# io-board-a-5.net
KiCad netlist of a schematic drawn in EAGLE
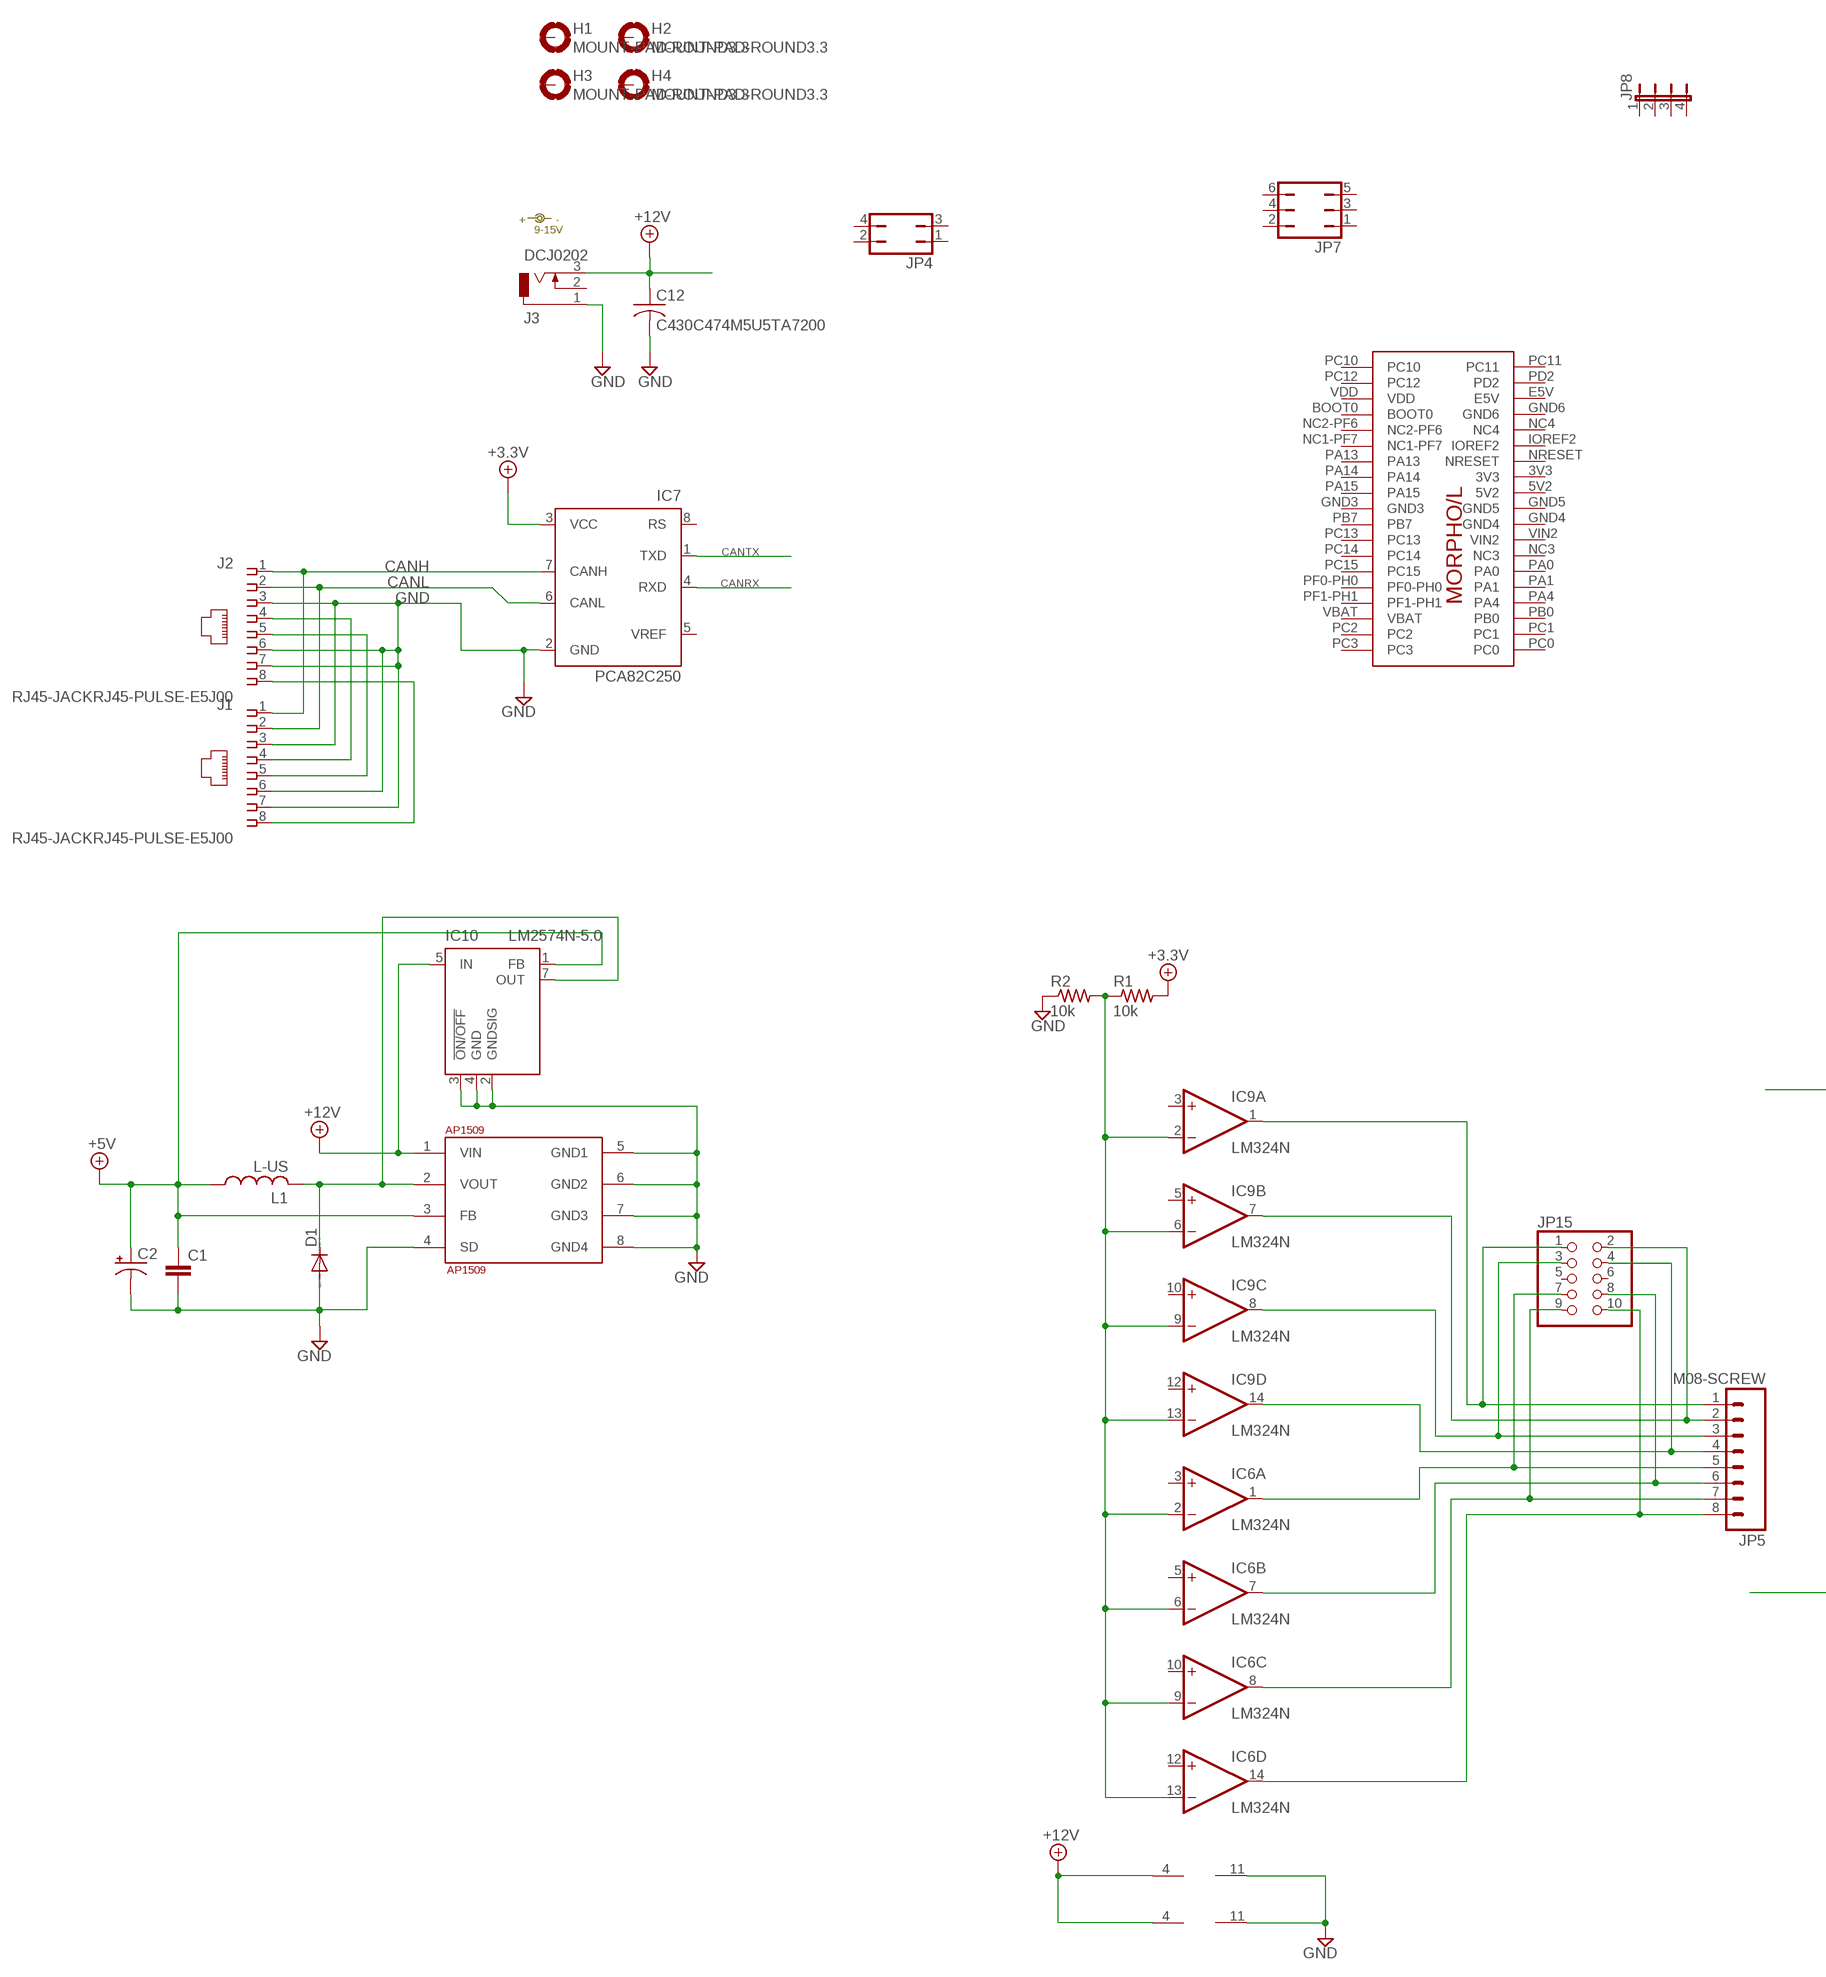
[diagram p0: schematic, sheet 1, part 1 of 2]
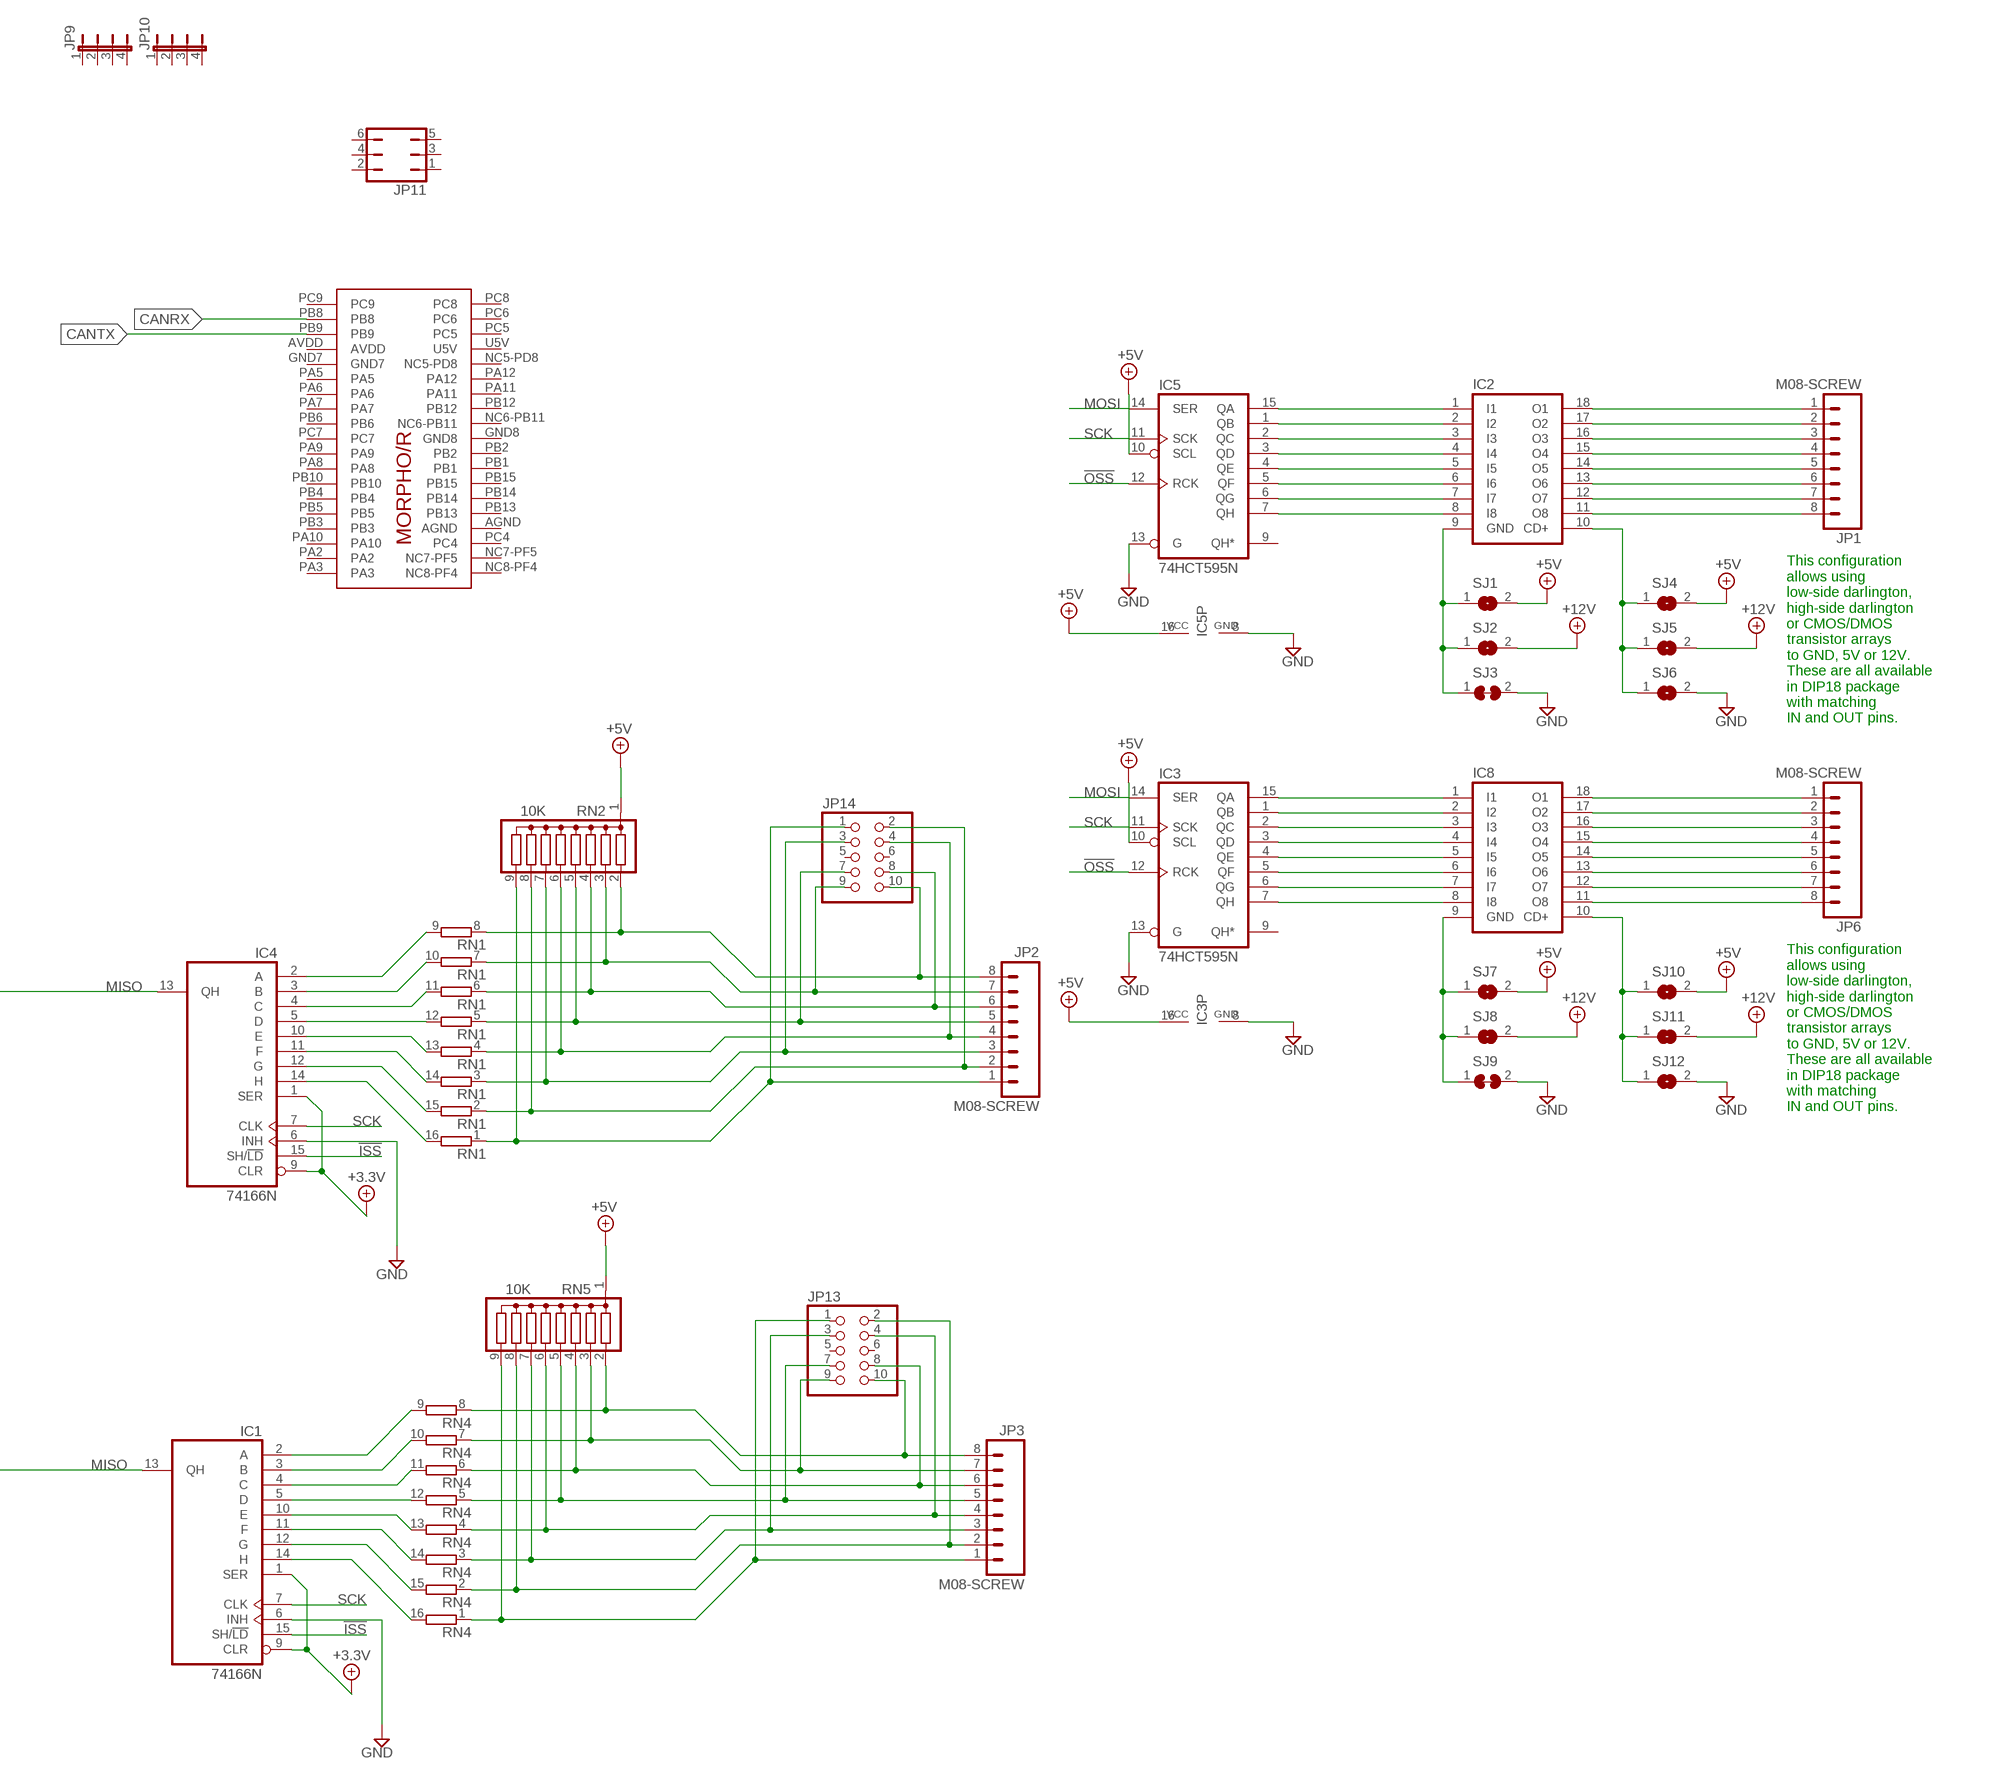
[diagram p1: schematic, sheet 1, part 2 of 2]

(export (version "E")
  (design (tool "Eeschema 10.0.6"))
  (components
    (comp (ref "+12V")
      (value "9-15V")
      (footprint "eagle-import:POWER_USAGE")
      (libsource (lib "eagle-import") (part "DOC-POWER_LABEL"))
    )
    (comp (ref "AP1509")
      (value "AP1509")
      (footprint "eagle-import:SO-08")
      (libsource (lib "eagle-import") (part "AP1509"))
    )
    (comp (ref "C1")
      (value "C-EUC1206")
      (footprint "eagle-import:C1206")
      (libsource (lib "eagle-import") (part "C-EUC1206"))
    )
    (comp (ref "C2")
      (value "CPOL-USE2.5-5")
      (footprint "eagle-import:E2,5-5")
      (libsource (lib "eagle-import") (part "CPOL-USE2.5-5"))
    )
    (comp (ref "C12")
      (value "C430C474M5U5TA7200")
      (footprint "eagle-import:C075-032X103")
      (libsource (lib "eagle-import") (part "C-US075-032X103"))
    )
    (comp (ref "D1")
      (value "DIODE-DO41-7.6")
      (footprint "eagle-import:DO41-7.6")
      (libsource (lib "eagle-import") (part "DIODE-DO41-7.6"))
    )
    (comp (ref "H1")
      (value "MOUNT-PAD-ROUND3.3")
      (footprint "eagle-import:3,3-PAD")
      (libsource (lib "eagle-import") (part "MOUNT-PAD-ROUND3.3"))
    )
    (comp (ref "H2")
      (value "MOUNT-PAD-ROUND3.3")
      (footprint "eagle-import:3,3-PAD")
      (libsource (lib "eagle-import") (part "MOUNT-PAD-ROUND3.3"))
    )
    (comp (ref "H3")
      (value "MOUNT-PAD-ROUND3.3")
      (footprint "eagle-import:3,3-PAD")
      (libsource (lib "eagle-import") (part "MOUNT-PAD-ROUND3.3"))
    )
    (comp (ref "H4")
      (value "MOUNT-PAD-ROUND3.3")
      (footprint "eagle-import:3,3-PAD")
      (libsource (lib "eagle-import") (part "MOUNT-PAD-ROUND3.3"))
    )
    (comp (ref "IC1")
      (value "74166N")
      (footprint "eagle-import:DIL16")
      (libsource (lib "eagle-import") (part "74166N"))
    )
    (comp (ref "IC2")
      (value "ULN2803A")
      (footprint "eagle-import:DIL18")
      (libsource (lib "eagle-import") (part "ULN2803A"))
    )
    (comp (ref "IC3")
      (value "74HCT595N")
      (footprint "eagle-import:DIL16")
      (libsource (lib "eagle-import") (part "74595NHCT"))
    )
    (comp (ref "IC4")
      (value "74166N")
      (footprint "eagle-import:DIL16")
      (libsource (lib "eagle-import") (part "74166N"))
    )
    (comp (ref "IC5")
      (value "74HCT595N")
      (footprint "eagle-import:DIL16")
      (libsource (lib "eagle-import") (part "74595NHCT"))
    )
    (comp (ref "IC6")
      (value "LM324N")
      (footprint "eagle-import:DIL14")
      (libsource (lib "eagle-import") (part "LM324N"))
    )
    (comp (ref "IC7")
      (value "PCA82C250")
      (footprint "eagle-import:DIL08")
      (libsource (lib "eagle-import") (part "PCA82C250"))
    )
    (comp (ref "IC8")
      (value "ULN2803A")
      (footprint "eagle-import:DIL18")
      (libsource (lib "eagle-import") (part "ULN2803A"))
    )
    (comp (ref "IC9")
      (value "LM324N")
      (footprint "eagle-import:DIL14")
      (libsource (lib "eagle-import") (part "LM324N"))
    )
    (comp (ref "IC10")
      (value "LM2574N-5.0")
      (footprint "eagle-import:DIL08")
      (libsource (lib "eagle-import") (part "LM2574?-N5.0"))
    )
    (comp (ref "J1")
      (value "RJ45-JACKRJ45-PULSE-E5J00")
      (footprint "eagle-import:RJ45-PULSE-E5J88")
      (libsource (lib "eagle-import") (part "RJ45-JACKRJ45-PULSE-E5J00"))
    )
    (comp (ref "J2")
      (value "RJ45-JACKRJ45-PULSE-E5J00")
      (footprint "eagle-import:RJ45-PULSE-E5J88")
      (libsource (lib "eagle-import") (part "RJ45-JACKRJ45-PULSE-E5J00"))
    )
    (comp (ref "J3")
      (value "DCJ0202")
      (footprint "eagle-import:DCJ0202")
      (libsource (lib "eagle-import") (part "DCJ0202"))
    )
    (comp (ref "JP1")
      (value "M08-SCREW")
      (footprint "eagle-import:1X08_TERMINAL")
      (libsource (lib "eagle-import") (part "M08-SCREW"))
    )
    (comp (ref "JP2")
      (value "M08-SCREW")
      (footprint "eagle-import:1X08_TERMINAL")
      (libsource (lib "eagle-import") (part "M08-SCREW"))
    )
    (comp (ref "JP3")
      (value "M08-SCREW")
      (footprint "eagle-import:1X08_TERMINAL")
      (libsource (lib "eagle-import") (part "M08-SCREW"))
    )
    (comp (ref "JP4")
      (value "JP2Q")
      (footprint "eagle-import:JP2Q")
      (libsource (lib "eagle-import") (part "JP2Q"))
    )
    (comp (ref "JP5")
      (value "M08-SCREW")
      (footprint "eagle-import:1X08_TERMINAL")
      (libsource (lib "eagle-import") (part "M08-SCREW"))
    )
    (comp (ref "JP6")
      (value "M08-SCREW")
      (footprint "eagle-import:1X08_TERMINAL")
      (libsource (lib "eagle-import") (part "M08-SCREW"))
    )
    (comp (ref "JP7")
      (value "JP3Q")
      (footprint "eagle-import:JP3Q")
      (libsource (lib "eagle-import") (part "JP3Q"))
    )
    (comp (ref "JP8")
      (value "JP4-FLAT")
      (footprint "eagle-import:JP4F")
      (libsource (lib "eagle-import") (part "JP4-FLAT"))
    )
    (comp (ref "JP9")
      (value "JP4-FLAT")
      (footprint "eagle-import:JP4F")
      (libsource (lib "eagle-import") (part "JP4-FLAT"))
    )
    (comp (ref "JP10")
      (value "JP4-FLAT")
      (footprint "eagle-import:JP4F")
      (libsource (lib "eagle-import") (part "JP4-FLAT"))
    )
    (comp (ref "JP11")
      (value "JP3Q")
      (footprint "eagle-import:JP3Q")
      (libsource (lib "eagle-import") (part "JP3Q"))
    )
    (comp (ref "JP13")
      (value "PINHD-2X5CN")
      (footprint "eagle-import:CON10M")
      (libsource (lib "eagle-import") (part "PINHD-2X5CN"))
    )
    (comp (ref "JP14")
      (value "PINHD-2X5CN")
      (footprint "eagle-import:CON10M")
      (libsource (lib "eagle-import") (part "PINHD-2X5CN"))
    )
    (comp (ref "JP15")
      (value "PINHD-2X5CN")
      (footprint "eagle-import:CON10M")
      (libsource (lib "eagle-import") (part "PINHD-2X5CN"))
    )
    (comp (ref "L1")
      (value "L-US")
      (footprint "eagle-import:L5-8,5")
      (libsource (lib "eagle-import") (part "L-US"))
    )
    (comp (ref "R1")
      (value "10k")
      (footprint "eagle-import:R1206")
      (libsource (lib "eagle-import") (part "R-US_R1206"))
    )
    (comp (ref "R2")
      (value "10k")
      (footprint "eagle-import:R1206")
      (libsource (lib "eagle-import") (part "R-US_R1206"))
    )
    (comp (ref "RN1")
      (value "8R-P")
      (footprint "eagle-import:DIL16")
      (libsource (lib "eagle-import") (part "8R-P"))
    )
    (comp (ref "RN2")
      (value "10K")
      (footprint "eagle-import:SIL9")
      (libsource (lib "eagle-import") (part "G08R"))
    )
    (comp (ref "RN4")
      (value "8R-P")
      (footprint "eagle-import:DIL16")
      (libsource (lib "eagle-import") (part "8R-P"))
    )
    (comp (ref "RN5")
      (value "10K")
      (footprint "eagle-import:SIL9")
      (libsource (lib "eagle-import") (part "G08R"))
    )
    (comp (ref "SJ1")
      (value "SJ")
      (footprint "eagle-import:SJ-RND")
      (libsource (lib "eagle-import") (part "SJ"))
    )
    (comp (ref "SJ2")
      (value "SJ")
      (footprint "eagle-import:SJ-RND")
      (libsource (lib "eagle-import") (part "SJ"))
    )
    (comp (ref "SJ3")
      (value "SJ-C")
      (footprint "eagle-import:SJW-C")
      (libsource (lib "eagle-import") (part "SJ-C"))
    )
    (comp (ref "SJ4")
      (value "SJ")
      (footprint "eagle-import:SJ-RND")
      (libsource (lib "eagle-import") (part "SJ"))
    )
    (comp (ref "SJ5")
      (value "SJ")
      (footprint "eagle-import:SJ-RND")
      (libsource (lib "eagle-import") (part "SJ"))
    )
    (comp (ref "SJ6")
      (value "SJ")
      (footprint "eagle-import:SJ-RND")
      (libsource (lib "eagle-import") (part "SJ"))
    )
    (comp (ref "SJ7")
      (value "SJ")
      (footprint "eagle-import:SJ-RND")
      (libsource (lib "eagle-import") (part "SJ"))
    )
    (comp (ref "SJ8")
      (value "SJ")
      (footprint "eagle-import:SJ-RND")
      (libsource (lib "eagle-import") (part "SJ"))
    )
    (comp (ref "SJ9")
      (value "SJ-C")
      (footprint "eagle-import:SJW-C")
      (libsource (lib "eagle-import") (part "SJ-C"))
    )
    (comp (ref "SJ10")
      (value "SJ")
      (footprint "eagle-import:SJ-RND")
      (libsource (lib "eagle-import") (part "SJ"))
    )
    (comp (ref "SJ11")
      (value "SJ")
      (footprint "eagle-import:SJ-RND")
      (libsource (lib "eagle-import") (part "SJ"))
    )
    (comp (ref "SJ12")
      (value "SJ")
      (footprint "eagle-import:SJ-RND")
      (libsource (lib "eagle-import") (part "SJ"))
    )
    (comp (ref "U$1")
      (value "NUCLEO_64_GENERIC")
      (footprint "eagle-import:NUCLEO_BRD_BASE64")
      (libsource (lib "eagle-import") (part "NUCLEO_64_GENERIC"))
    )
  )
  (nets
    (net (code "1") (name "+3.3V") (class "Default")
      (node (ref "IC1") (pin "1") (pinfunction "SER_1") (pintype "input"))
      (node (ref "IC1") (pin "9") (pinfunction "CLR_9") (pintype "input"))
      (node (ref "IC4") (pin "1") (pinfunction "SER_1") (pintype "input"))
      (node (ref "IC4") (pin "9") (pinfunction "CLR_9") (pintype "input"))
      (node (ref "IC7") (pin "3") (pinfunction "VCC_3") (pintype "power_in"))
      (node (ref "R1") (pin "2") (pinfunction "2_2") (pintype "passive"))
    )
    (net (code "2") (name "+5V") (class "Default")
      (node (ref "AP1509") (pin "3") (pinfunction "FB_3") (pintype "bidirectional"))
      (node (ref "C1") (pin "1") (pinfunction "1_1") (pintype "passive"))
      (node (ref "C2") (pin "+") (pinfunction "+_+") (pintype "passive"))
      (node (ref "IC10") (pin "1") (pinfunction "FB_1") (pintype "input"))
      (node (ref "IC3") (pin "10") (pinfunction "SCL_10") (pintype "input"))
      (node (ref "IC3") (pin "16") (pinfunction "VCC_16") (pintype "power_in"))
      (node (ref "IC5") (pin "10") (pinfunction "SCL_10") (pintype "input"))
      (node (ref "IC5") (pin "16") (pinfunction "VCC_16") (pintype "power_in"))
      (node (ref "L1") (pin "1") (pinfunction "1_1") (pintype "passive"))
      (node (ref "RN2") (pin "1") (pinfunction "1_1") (pintype "passive"))
      (node (ref "RN5") (pin "1") (pinfunction "1_1") (pintype "passive"))
      (node (ref "SJ1") (pin "2") (pinfunction "2_2") (pintype "passive"))
      (node (ref "SJ10") (pin "2") (pinfunction "2_2") (pintype "passive"))
      (node (ref "SJ4") (pin "2") (pinfunction "2_2") (pintype "passive"))
      (node (ref "SJ7") (pin "2") (pinfunction "2_2") (pintype "passive"))
    )
    (net (code "3") (name "+12V") (class "Default")
      (node (ref "AP1509") (pin "1") (pinfunction "VIN_1") (pintype "bidirectional"))
      (node (ref "C12") (pin "1") (pinfunction "1_1") (pintype "passive"))
      (node (ref "IC10") (pin "5") (pinfunction "IN_5") (pintype "input"))
      (node (ref "IC6") (pin "4") (pinfunction "V+_4") (pintype "power_in"))
      (node (ref "IC9") (pin "4") (pinfunction "V+_4") (pintype "power_in"))
      (node (ref "J3") (pin "3") (pinfunction "3_3") (pintype "passive"))
      (node (ref "SJ11") (pin "2") (pinfunction "2_2") (pintype "passive"))
      (node (ref "SJ2") (pin "2") (pinfunction "2_2") (pintype "passive"))
      (node (ref "SJ5") (pin "2") (pinfunction "2_2") (pintype "passive"))
      (node (ref "SJ8") (pin "2") (pinfunction "2_2") (pintype "passive"))
    )
    (net (code "4") (name "/3V3") (class "Default")
      (node (ref "U$1") (pin "3V3") (pinfunction "3V3_3V3") (pintype "power_in"))
    )
    (net (code "5") (name "/5V2") (class "Default")
      (node (ref "U$1") (pin "5V2") (pinfunction "5V2_5V2") (pintype "power_in"))
    )
    (net (code "6") (name "/AGND") (class "Default")
      (node (ref "U$1") (pin "AGND") (pinfunction "AGND_AGND") (pintype "power_in"))
    )
    (net (code "7") (name "/AVDD") (class "Default")
      (node (ref "U$1") (pin "AVDD") (pinfunction "AVDD_AVDD") (pintype "power_in"))
    )
    (net (code "8") (name "/CANH") (class "Default")
      (node (ref "IC7") (pin "7") (pinfunction "CANH_7") (pintype "bidirectional"))
      (node (ref "J1") (pin "1") (pinfunction "1_1") (pintype "passive"))
      (node (ref "J2") (pin "1") (pinfunction "1_1") (pintype "passive"))
    )
    (net (code "9") (name "/CANL") (class "Default")
      (node (ref "IC7") (pin "6") (pinfunction "CANL_6") (pintype "bidirectional"))
      (node (ref "J1") (pin "2") (pinfunction "2_2") (pintype "passive"))
      (node (ref "J2") (pin "2") (pinfunction "2_2") (pintype "passive"))
    )
    (net (code "10") (name "/E5V") (class "Default")
      (node (ref "U$1") (pin "E5V") (pinfunction "E5V_E5V") (pintype "power_in"))
    )
    (net (code "11") (name "/GND3") (class "Default")
      (node (ref "U$1") (pin "GND3") (pinfunction "GND3_GND3") (pintype "power_in"))
    )
    (net (code "12") (name "/GND4") (class "Default")
      (node (ref "U$1") (pin "GND4") (pinfunction "GND4_GND4") (pintype "power_in"))
    )
    (net (code "13") (name "/GND5") (class "Default")
      (node (ref "U$1") (pin "GND5") (pinfunction "GND5_GND5") (pintype "power_in"))
    )
    (net (code "14") (name "/GND6") (class "Default")
      (node (ref "U$1") (pin "GND6") (pinfunction "GND6_GND6") (pintype "power_in"))
    )
    (net (code "15") (name "/GND7") (class "Default")
      (node (ref "U$1") (pin "GND7") (pinfunction "GND7_GND7") (pintype "power_in"))
    )
    (net (code "16") (name "/GND8") (class "Default")
      (node (ref "U$1") (pin "GND8") (pinfunction "GND8_GND8") (pintype "power_in"))
    )
    (net (code "17") (name "/MISO") (class "Default")
      (node (ref "IC1") (pin "13") (pinfunction "QH_13") (pintype "output"))
      (node (ref "IC4") (pin "13") (pinfunction "QH_13") (pintype "output"))
    )
    (net (code "18") (name "/MOSI") (class "Default")
      (node (ref "IC3") (pin "14") (pinfunction "SER_14") (pintype "input"))
      (node (ref "IC5") (pin "14") (pinfunction "SER_14") (pintype "input"))
    )
    (net (code "19") (name "/SCK") (class "Default")
      (node (ref "IC1") (pin "7") (pinfunction "CLK_7") (pintype "input"))
      (node (ref "IC3") (pin "11") (pinfunction "SCK_11") (pintype "input"))
      (node (ref "IC4") (pin "7") (pinfunction "CLK_7") (pintype "input"))
      (node (ref "IC5") (pin "11") (pinfunction "SCK_11") (pintype "input"))
    )
    (net (code "20") (name "/U5V") (class "Default")
      (node (ref "U$1") (pin "U5V") (pinfunction "U5V_U5V") (pintype "power_in"))
    )
    (net (code "21") (name "/VBAT") (class "Default")
      (node (ref "U$1") (pin "VBAT") (pinfunction "VBAT_VBAT") (pintype "power_in"))
    )
    (net (code "22") (name "/VDD") (class "Default")
      (node (ref "U$1") (pin "VDD") (pinfunction "VDD_VDD") (pintype "power_in"))
    )
    (net (code "23") (name "/VIN2") (class "Default")
      (node (ref "U$1") (pin "VIN2") (pinfunction "VIN2_VIN2") (pintype "power_in"))
    )
    (net (code "24") (name "/~{ISS}") (class "Default")
      (node (ref "IC1") (pin "15") (pinfunction "SH/~{LD}_15") (pintype "input"))
      (node (ref "IC4") (pin "15") (pinfunction "SH/~{LD}_15") (pintype "input"))
    )
    (net (code "25") (name "/~{OSS}") (class "Default")
      (node (ref "IC3") (pin "12") (pinfunction "RCK_12") (pintype "input"))
      (node (ref "IC5") (pin "12") (pinfunction "RCK_12") (pintype "input"))
    )
    (net (code "26") (name "CANRX") (class "Default")
      (node (ref "IC7") (pin "4") (pinfunction "RXD_4") (pintype "output"))
      (node (ref "U$1") (pin "PB8") (pinfunction "PB8_PB8") (pintype "bidirectional"))
    )
    (net (code "27") (name "CANTX") (class "Default")
      (node (ref "IC7") (pin "1") (pinfunction "TXD_1") (pintype "input"))
      (node (ref "U$1") (pin "PB9") (pinfunction "PB9_PB9") (pintype "bidirectional"))
    )
    (net (code "28") (name "GND") (class "Default")
      (node (ref "AP1509") (pin "4") (pinfunction "SD_4") (pintype "bidirectional"))
      (node (ref "AP1509") (pin "5") (pinfunction "GND1_5") (pintype "power_in"))
      (node (ref "AP1509") (pin "6") (pinfunction "GND2_6") (pintype "power_in"))
      (node (ref "AP1509") (pin "7") (pinfunction "GND3_7") (pintype "power_in"))
      (node (ref "AP1509") (pin "8") (pinfunction "GND4_8") (pintype "power_in"))
      (node (ref "C1") (pin "2") (pinfunction "2_2") (pintype "passive"))
      (node (ref "C12") (pin "2") (pinfunction "2_2") (pintype "passive"))
      (node (ref "C2") (pin "-") (pinfunction "-_-") (pintype "passive"))
      (node (ref "D1") (pin "A") (pinfunction "A_A") (pintype "passive"))
      (node (ref "IC1") (pin "6") (pinfunction "INH_6") (pintype "input"))
      (node (ref "IC10") (pin "2") (pinfunction "GNDSIG_2") (pintype "input"))
      (node (ref "IC10") (pin "3") (pinfunction "~{ON/OFF}_3") (pintype "input"))
      (node (ref "IC10") (pin "4") (pinfunction "GND_4") (pintype "power_in"))
      (node (ref "IC3") (pin "13") (pinfunction "G_13") (pintype "input"))
      (node (ref "IC3") (pin "8") (pinfunction "GND_8") (pintype "power_in"))
      (node (ref "IC4") (pin "6") (pinfunction "INH_6") (pintype "input"))
      (node (ref "IC5") (pin "13") (pinfunction "G_13") (pintype "input"))
      (node (ref "IC5") (pin "8") (pinfunction "GND_8") (pintype "power_in"))
      (node (ref "IC6") (pin "11") (pinfunction "V-_11") (pintype "power_in"))
      (node (ref "IC7") (pin "2") (pinfunction "GND_2") (pintype "power_in"))
      (node (ref "IC9") (pin "11") (pinfunction "V-_11") (pintype "power_in"))
      (node (ref "J1") (pin "3") (pinfunction "3_3") (pintype "passive"))
      (node (ref "J1") (pin "6") (pinfunction "6_6") (pintype "passive"))
      (node (ref "J1") (pin "7") (pinfunction "7_7") (pintype "passive"))
      (node (ref "J2") (pin "3") (pinfunction "3_3") (pintype "passive"))
      (node (ref "J2") (pin "6") (pinfunction "6_6") (pintype "passive"))
      (node (ref "J2") (pin "7") (pinfunction "7_7") (pintype "passive"))
      (node (ref "J3") (pin "1") (pinfunction "1_1") (pintype "passive"))
      (node (ref "R2") (pin "1") (pinfunction "1_1") (pintype "passive"))
      (node (ref "SJ12") (pin "2") (pinfunction "2_2") (pintype "passive"))
      (node (ref "SJ3") (pin "2") (pinfunction "2_2") (pintype "passive"))
      (node (ref "SJ6") (pin "2") (pinfunction "2_2") (pintype "passive"))
      (node (ref "SJ9") (pin "2") (pinfunction "2_2") (pintype "passive"))
    )
    (net (code "29") (name "Net-(AP1509-VOUT)") (class "Default")
      (node (ref "AP1509") (pin "2") (pinfunction "VOUT_2") (pintype "bidirectional"))
      (node (ref "D1") (pin "C") (pinfunction "C_C") (pintype "passive"))
      (node (ref "IC10") (pin "7") (pinfunction "OUT_7") (pintype "passive"))
      (node (ref "L1") (pin "2") (pinfunction "2_2") (pintype "passive"))
    )
    (net (code "30") (name "Net-(IC1A-A)") (class "Default")
      (node (ref "IC1") (pin "2") (pinfunction "A_2") (pintype "input"))
      (node (ref "RN4") (pin "9") (pinfunction "2_9") (pintype "passive"))
    )
    (net (code "31") (name "Net-(IC1A-B)") (class "Default")
      (node (ref "IC1") (pin "3") (pinfunction "B_3") (pintype "input"))
      (node (ref "RN4") (pin "10") (pinfunction "2_10") (pintype "passive"))
    )
    (net (code "32") (name "Net-(IC1A-C)") (class "Default")
      (node (ref "IC1") (pin "4") (pinfunction "C_4") (pintype "input"))
      (node (ref "RN4") (pin "11") (pinfunction "2_11") (pintype "passive"))
    )
    (net (code "33") (name "Net-(IC1A-D)") (class "Default")
      (node (ref "IC1") (pin "5") (pinfunction "D_5") (pintype "input"))
      (node (ref "RN4") (pin "12") (pinfunction "2_12") (pintype "passive"))
    )
    (net (code "34") (name "Net-(IC1A-E)") (class "Default")
      (node (ref "IC1") (pin "10") (pinfunction "E_10") (pintype "input"))
      (node (ref "RN4") (pin "13") (pinfunction "2_13") (pintype "passive"))
    )
    (net (code "35") (name "Net-(IC1A-F)") (class "Default")
      (node (ref "IC1") (pin "11") (pinfunction "F_11") (pintype "input"))
      (node (ref "RN4") (pin "14") (pinfunction "2_14") (pintype "passive"))
    )
    (net (code "36") (name "Net-(IC1A-G)") (class "Default")
      (node (ref "IC1") (pin "12") (pinfunction "G_12") (pintype "input"))
      (node (ref "RN4") (pin "15") (pinfunction "2_15") (pintype "passive"))
    )
    (net (code "37") (name "Net-(IC1A-H)") (class "Default")
      (node (ref "IC1") (pin "14") (pinfunction "H_14") (pintype "input"))
      (node (ref "RN4") (pin "16") (pinfunction "2_16") (pintype "passive"))
    )
    (net (code "38") (name "Net-(IC2-CD+)") (class "Default")
      (node (ref "IC2") (pin "10") (pinfunction "CD+_10") (pintype "passive"))
      (node (ref "SJ4") (pin "1") (pinfunction "1_1") (pintype "passive"))
      (node (ref "SJ5") (pin "1") (pinfunction "1_1") (pintype "passive"))
      (node (ref "SJ6") (pin "1") (pinfunction "1_1") (pintype "passive"))
    )
    (net (code "39") (name "Net-(IC2-GND)") (class "Default")
      (node (ref "IC2") (pin "9") (pinfunction "GND_9") (pintype "power_in"))
      (node (ref "SJ1") (pin "1") (pinfunction "1_1") (pintype "passive"))
      (node (ref "SJ2") (pin "1") (pinfunction "1_1") (pintype "passive"))
      (node (ref "SJ3") (pin "1") (pinfunction "1_1") (pintype "passive"))
    )
    (net (code "40") (name "Net-(IC2-I1)") (class "Default")
      (node (ref "IC2") (pin "1") (pinfunction "I1_1") (pintype "input"))
      (node (ref "IC5") (pin "15") (pinfunction "QA_15") (pintype "tri_state"))
    )
    (net (code "41") (name "Net-(IC2-I2)") (class "Default")
      (node (ref "IC2") (pin "2") (pinfunction "I2_2") (pintype "input"))
      (node (ref "IC5") (pin "1") (pinfunction "QB_1") (pintype "tri_state"))
    )
    (net (code "42") (name "Net-(IC2-I3)") (class "Default")
      (node (ref "IC2") (pin "3") (pinfunction "I3_3") (pintype "input"))
      (node (ref "IC5") (pin "2") (pinfunction "QC_2") (pintype "tri_state"))
    )
    (net (code "43") (name "Net-(IC2-I4)") (class "Default")
      (node (ref "IC2") (pin "4") (pinfunction "I4_4") (pintype "input"))
      (node (ref "IC5") (pin "3") (pinfunction "QD_3") (pintype "tri_state"))
    )
    (net (code "44") (name "Net-(IC2-I5)") (class "Default")
      (node (ref "IC2") (pin "5") (pinfunction "I5_5") (pintype "input"))
      (node (ref "IC5") (pin "4") (pinfunction "QE_4") (pintype "tri_state"))
    )
    (net (code "45") (name "Net-(IC2-I6)") (class "Default")
      (node (ref "IC2") (pin "6") (pinfunction "I6_6") (pintype "input"))
      (node (ref "IC5") (pin "5") (pinfunction "QF_5") (pintype "tri_state"))
    )
    (net (code "46") (name "Net-(IC2-I7)") (class "Default")
      (node (ref "IC2") (pin "7") (pinfunction "I7_7") (pintype "input"))
      (node (ref "IC5") (pin "6") (pinfunction "QG_6") (pintype "tri_state"))
    )
    (net (code "47") (name "Net-(IC2-I8)") (class "Default")
      (node (ref "IC2") (pin "8") (pinfunction "I8_8") (pintype "input"))
      (node (ref "IC5") (pin "7") (pinfunction "QH_7") (pintype "tri_state"))
    )
    (net (code "48") (name "Net-(IC2-O1)") (class "Default")
      (node (ref "IC2") (pin "18") (pinfunction "O1_18") (pintype "open_collector"))
      (node (ref "JP1") (pin "1") (pinfunction "1_1") (pintype "passive"))
    )
    (net (code "49") (name "Net-(IC2-O2)") (class "Default")
      (node (ref "IC2") (pin "17") (pinfunction "O2_17") (pintype "open_collector"))
      (node (ref "JP1") (pin "2") (pinfunction "2_2") (pintype "passive"))
    )
    (net (code "50") (name "Net-(IC2-O3)") (class "Default")
      (node (ref "IC2") (pin "16") (pinfunction "O3_16") (pintype "open_collector"))
      (node (ref "JP1") (pin "3") (pinfunction "3_3") (pintype "passive"))
    )
    (net (code "51") (name "Net-(IC2-O4)") (class "Default")
      (node (ref "IC2") (pin "15") (pinfunction "O4_15") (pintype "open_collector"))
      (node (ref "JP1") (pin "4") (pinfunction "4_4") (pintype "passive"))
    )
    (net (code "52") (name "Net-(IC2-O5)") (class "Default")
      (node (ref "IC2") (pin "14") (pinfunction "O5_14") (pintype "open_collector"))
      (node (ref "JP1") (pin "5") (pinfunction "5_5") (pintype "passive"))
    )
    (net (code "53") (name "Net-(IC2-O6)") (class "Default")
      (node (ref "IC2") (pin "13") (pinfunction "O6_13") (pintype "open_collector"))
      (node (ref "JP1") (pin "6") (pinfunction "6_6") (pintype "passive"))
    )
    (net (code "54") (name "Net-(IC2-O7)") (class "Default")
      (node (ref "IC2") (pin "12") (pinfunction "O7_12") (pintype "open_collector"))
      (node (ref "JP1") (pin "7") (pinfunction "7_7") (pintype "passive"))
    )
    (net (code "55") (name "Net-(IC2-O8)") (class "Default")
      (node (ref "IC2") (pin "11") (pinfunction "O8_11") (pintype "open_collector"))
      (node (ref "JP1") (pin "8") (pinfunction "8_8") (pintype "passive"))
    )
    (net (code "56") (name "Net-(IC3A-QA)") (class "Default")
      (node (ref "IC3") (pin "15") (pinfunction "QA_15") (pintype "tri_state"))
      (node (ref "IC8") (pin "1") (pinfunction "I1_1") (pintype "input"))
    )
    (net (code "57") (name "Net-(IC3A-QB)") (class "Default")
      (node (ref "IC3") (pin "1") (pinfunction "QB_1") (pintype "tri_state"))
      (node (ref "IC8") (pin "2") (pinfunction "I2_2") (pintype "input"))
    )
    (net (code "58") (name "Net-(IC3A-QC)") (class "Default")
      (node (ref "IC3") (pin "2") (pinfunction "QC_2") (pintype "tri_state"))
      (node (ref "IC8") (pin "3") (pinfunction "I3_3") (pintype "input"))
    )
    (net (code "59") (name "Net-(IC3A-QD)") (class "Default")
      (node (ref "IC3") (pin "3") (pinfunction "QD_3") (pintype "tri_state"))
      (node (ref "IC8") (pin "4") (pinfunction "I4_4") (pintype "input"))
    )
    (net (code "60") (name "Net-(IC3A-QE)") (class "Default")
      (node (ref "IC3") (pin "4") (pinfunction "QE_4") (pintype "tri_state"))
      (node (ref "IC8") (pin "5") (pinfunction "I5_5") (pintype "input"))
    )
    (net (code "61") (name "Net-(IC3A-QF)") (class "Default")
      (node (ref "IC3") (pin "5") (pinfunction "QF_5") (pintype "tri_state"))
      (node (ref "IC8") (pin "6") (pinfunction "I6_6") (pintype "input"))
    )
    (net (code "62") (name "Net-(IC3A-QG)") (class "Default")
      (node (ref "IC3") (pin "6") (pinfunction "QG_6") (pintype "tri_state"))
      (node (ref "IC8") (pin "7") (pinfunction "I7_7") (pintype "input"))
    )
    (net (code "63") (name "Net-(IC3A-QH)") (class "Default")
      (node (ref "IC3") (pin "7") (pinfunction "QH_7") (pintype "tri_state"))
      (node (ref "IC8") (pin "8") (pinfunction "I8_8") (pintype "input"))
    )
    (net (code "64") (name "Net-(IC4A-A)") (class "Default")
      (node (ref "IC4") (pin "2") (pinfunction "A_2") (pintype "input"))
      (node (ref "RN1") (pin "9") (pinfunction "2_9") (pintype "passive"))
    )
    (net (code "65") (name "Net-(IC4A-B)") (class "Default")
      (node (ref "IC4") (pin "3") (pinfunction "B_3") (pintype "input"))
      (node (ref "RN1") (pin "10") (pinfunction "2_10") (pintype "passive"))
    )
    (net (code "66") (name "Net-(IC4A-C)") (class "Default")
      (node (ref "IC4") (pin "4") (pinfunction "C_4") (pintype "input"))
      (node (ref "RN1") (pin "11") (pinfunction "2_11") (pintype "passive"))
    )
    (net (code "67") (name "Net-(IC4A-D)") (class "Default")
      (node (ref "IC4") (pin "5") (pinfunction "D_5") (pintype "input"))
      (node (ref "RN1") (pin "12") (pinfunction "2_12") (pintype "passive"))
    )
    (net (code "68") (name "Net-(IC4A-E)") (class "Default")
      (node (ref "IC4") (pin "10") (pinfunction "E_10") (pintype "input"))
      (node (ref "RN1") (pin "13") (pinfunction "2_13") (pintype "passive"))
    )
    (net (code "69") (name "Net-(IC4A-F)") (class "Default")
      (node (ref "IC4") (pin "11") (pinfunction "F_11") (pintype "input"))
      (node (ref "RN1") (pin "14") (pinfunction "2_14") (pintype "passive"))
    )
    (net (code "70") (name "Net-(IC4A-G)") (class "Default")
      (node (ref "IC4") (pin "12") (pinfunction "G_12") (pintype "input"))
      (node (ref "RN1") (pin "15") (pinfunction "2_15") (pintype "passive"))
    )
    (net (code "71") (name "Net-(IC4A-H)") (class "Default")
      (node (ref "IC4") (pin "14") (pinfunction "H_14") (pintype "input"))
      (node (ref "RN1") (pin "16") (pinfunction "2_16") (pintype "passive"))
    )
    (net (code "72") (name "Net-(IC6A--IN)") (class "Default")
      (node (ref "IC6") (pin "13") (pinfunction "-IN_13") (pintype "input"))
      (node (ref "IC6") (pin "2") (pinfunction "-IN_2") (pintype "input"))
      (node (ref "IC6") (pin "6") (pinfunction "-IN_6") (pintype "input"))
      (node (ref "IC6") (pin "9") (pinfunction "-IN_9") (pintype "input"))
      (node (ref "IC9") (pin "13") (pinfunction "-IN_13") (pintype "input"))
      (node (ref "IC9") (pin "2") (pinfunction "-IN_2") (pintype "input"))
      (node (ref "IC9") (pin "6") (pinfunction "-IN_6") (pintype "input"))
      (node (ref "IC9") (pin "9") (pinfunction "-IN_9") (pintype "input"))
      (node (ref "R1") (pin "1") (pinfunction "1_1") (pintype "passive"))
      (node (ref "R2") (pin "2") (pinfunction "2_2") (pintype "passive"))
    )
    (net (code "73") (name "Net-(IC6A-OUT)") (class "Default")
      (node (ref "IC6") (pin "1") (pinfunction "OUT_1") (pintype "output"))
      (node (ref "JP15") (pin "7") (pinfunction "7_7") (pintype "passive"))
      (node (ref "JP5") (pin "5") (pinfunction "5_5") (pintype "passive"))
    )
    (net (code "74") (name "Net-(IC6B-OUT)") (class "Default")
      (node (ref "IC6") (pin "7") (pinfunction "OUT_7") (pintype "output"))
      (node (ref "JP15") (pin "8") (pinfunction "8_8") (pintype "passive"))
      (node (ref "JP5") (pin "6") (pinfunction "6_6") (pintype "passive"))
    )
    (net (code "75") (name "Net-(IC6C-OUT)") (class "Default")
      (node (ref "IC6") (pin "8") (pinfunction "OUT_8") (pintype "output"))
      (node (ref "JP15") (pin "9") (pinfunction "9_9") (pintype "passive"))
      (node (ref "JP5") (pin "7") (pinfunction "7_7") (pintype "passive"))
    )
    (net (code "76") (name "Net-(IC6D-OUT)") (class "Default")
      (node (ref "IC6") (pin "14") (pinfunction "OUT_14") (pintype "output"))
      (node (ref "JP15") (pin "10") (pinfunction "10_10") (pintype "passive"))
      (node (ref "JP5") (pin "8") (pinfunction "8_8") (pintype "passive"))
    )
    (net (code "77") (name "Net-(IC8-CD+)") (class "Default")
      (node (ref "IC8") (pin "10") (pinfunction "CD+_10") (pintype "passive"))
      (node (ref "SJ10") (pin "1") (pinfunction "1_1") (pintype "passive"))
      (node (ref "SJ11") (pin "1") (pinfunction "1_1") (pintype "passive"))
      (node (ref "SJ12") (pin "1") (pinfunction "1_1") (pintype "passive"))
    )
    (net (code "78") (name "Net-(IC8-GND)") (class "Default")
      (node (ref "IC8") (pin "9") (pinfunction "GND_9") (pintype "power_in"))
      (node (ref "SJ7") (pin "1") (pinfunction "1_1") (pintype "passive"))
      (node (ref "SJ8") (pin "1") (pinfunction "1_1") (pintype "passive"))
      (node (ref "SJ9") (pin "1") (pinfunction "1_1") (pintype "passive"))
    )
    (net (code "79") (name "Net-(IC8-O1)") (class "Default")
      (node (ref "IC8") (pin "18") (pinfunction "O1_18") (pintype "open_collector"))
      (node (ref "JP6") (pin "1") (pinfunction "1_1") (pintype "passive"))
    )
    (net (code "80") (name "Net-(IC8-O2)") (class "Default")
      (node (ref "IC8") (pin "17") (pinfunction "O2_17") (pintype "open_collector"))
      (node (ref "JP6") (pin "2") (pinfunction "2_2") (pintype "passive"))
    )
    (net (code "81") (name "Net-(IC8-O3)") (class "Default")
      (node (ref "IC8") (pin "16") (pinfunction "O3_16") (pintype "open_collector"))
      (node (ref "JP6") (pin "3") (pinfunction "3_3") (pintype "passive"))
    )
    (net (code "82") (name "Net-(IC8-O4)") (class "Default")
      (node (ref "IC8") (pin "15") (pinfunction "O4_15") (pintype "open_collector"))
      (node (ref "JP6") (pin "4") (pinfunction "4_4") (pintype "passive"))
    )
    (net (code "83") (name "Net-(IC8-O5)") (class "Default")
      (node (ref "IC8") (pin "14") (pinfunction "O5_14") (pintype "open_collector"))
      (node (ref "JP6") (pin "5") (pinfunction "5_5") (pintype "passive"))
    )
    (net (code "84") (name "Net-(IC8-O6)") (class "Default")
      (node (ref "IC8") (pin "13") (pinfunction "O6_13") (pintype "open_collector"))
      (node (ref "JP6") (pin "6") (pinfunction "6_6") (pintype "passive"))
    )
    (net (code "85") (name "Net-(IC8-O7)") (class "Default")
      (node (ref "IC8") (pin "12") (pinfunction "O7_12") (pintype "open_collector"))
      (node (ref "JP6") (pin "7") (pinfunction "7_7") (pintype "passive"))
    )
    (net (code "86") (name "Net-(IC8-O8)") (class "Default")
      (node (ref "IC8") (pin "11") (pinfunction "O8_11") (pintype "open_collector"))
      (node (ref "JP6") (pin "8") (pinfunction "8_8") (pintype "passive"))
    )
    (net (code "87") (name "Net-(IC9A-OUT)") (class "Default")
      (node (ref "IC9") (pin "1") (pinfunction "OUT_1") (pintype "output"))
      (node (ref "JP15") (pin "1") (pinfunction "1_1") (pintype "passive"))
      (node (ref "JP5") (pin "1") (pinfunction "1_1") (pintype "passive"))
    )
    (net (code "88") (name "Net-(IC9B-OUT)") (class "Default")
      (node (ref "IC9") (pin "7") (pinfunction "OUT_7") (pintype "output"))
      (node (ref "JP15") (pin "2") (pinfunction "2_2") (pintype "passive"))
      (node (ref "JP5") (pin "2") (pinfunction "2_2") (pintype "passive"))
    )
    (net (code "89") (name "Net-(IC9C-OUT)") (class "Default")
      (node (ref "IC9") (pin "8") (pinfunction "OUT_8") (pintype "output"))
      (node (ref "JP15") (pin "3") (pinfunction "3_3") (pintype "passive"))
      (node (ref "JP5") (pin "3") (pinfunction "3_3") (pintype "passive"))
    )
    (net (code "90") (name "Net-(IC9D-OUT)") (class "Default")
      (node (ref "IC9") (pin "14") (pinfunction "OUT_14") (pintype "output"))
      (node (ref "JP15") (pin "4") (pinfunction "4_4") (pintype "passive"))
      (node (ref "JP5") (pin "4") (pinfunction "4_4") (pintype "passive"))
    )
    (net (code "91") (name "Net-(J1-Pad4)") (class "Default")
      (node (ref "J1") (pin "4") (pinfunction "4_4") (pintype "passive"))
      (node (ref "J2") (pin "4") (pinfunction "4_4") (pintype "passive"))
    )
    (net (code "92") (name "Net-(J1-Pad5)") (class "Default")
      (node (ref "J1") (pin "5") (pinfunction "5_5") (pintype "passive"))
      (node (ref "J2") (pin "5") (pinfunction "5_5") (pintype "passive"))
    )
    (net (code "93") (name "Net-(J1-Pad8)") (class "Default")
      (node (ref "J1") (pin "8") (pinfunction "8_8") (pintype "passive"))
      (node (ref "J2") (pin "8") (pinfunction "8_8") (pintype "passive"))
    )
    (net (code "94") (name "Net-(JP13-Pad1)") (class "Default")
      (node (ref "JP13") (pin "1") (pinfunction "1_1") (pintype "passive"))
      (node (ref "JP3") (pin "1") (pinfunction "1_1") (pintype "passive"))
      (node (ref "RN4") (pin "1") (pinfunction "1_1") (pintype "passive"))
      (node (ref "RN5") (pin "9") (pinfunction "9_9") (pintype "passive"))
    )
    (net (code "95") (name "Net-(JP14-Pad1)") (class "Default")
      (node (ref "JP14") (pin "1") (pinfunction "1_1") (pintype "passive"))
      (node (ref "JP2") (pin "1") (pinfunction "1_1") (pintype "passive"))
      (node (ref "RN1") (pin "1") (pinfunction "1_1") (pintype "passive"))
      (node (ref "RN2") (pin "9") (pinfunction "9_9") (pintype "passive"))
    )
    (net (code "96") (name "Net-(RN1B-1)") (class "Default")
      (node (ref "JP14") (pin "2") (pinfunction "2_2") (pintype "passive"))
      (node (ref "JP2") (pin "2") (pinfunction "2_2") (pintype "passive"))
      (node (ref "RN1") (pin "2") (pinfunction "1_2") (pintype "passive"))
      (node (ref "RN2") (pin "8") (pinfunction "8_8") (pintype "passive"))
    )
    (net (code "97") (name "Net-(RN1C-1)") (class "Default")
      (node (ref "JP14") (pin "3") (pinfunction "3_3") (pintype "passive"))
      (node (ref "JP2") (pin "3") (pinfunction "3_3") (pintype "passive"))
      (node (ref "RN1") (pin "3") (pinfunction "1_3") (pintype "passive"))
      (node (ref "RN2") (pin "7") (pinfunction "7_7") (pintype "passive"))
    )
    (net (code "98") (name "Net-(RN1D-1)") (class "Default")
      (node (ref "JP14") (pin "4") (pinfunction "4_4") (pintype "passive"))
      (node (ref "JP2") (pin "4") (pinfunction "4_4") (pintype "passive"))
      (node (ref "RN1") (pin "4") (pinfunction "1_4") (pintype "passive"))
      (node (ref "RN2") (pin "6") (pinfunction "6_6") (pintype "passive"))
    )
    (net (code "99") (name "Net-(RN1E-1)") (class "Default")
      (node (ref "JP14") (pin "7") (pinfunction "7_7") (pintype "passive"))
      (node (ref "JP2") (pin "5") (pinfunction "5_5") (pintype "passive"))
      (node (ref "RN1") (pin "5") (pinfunction "1_5") (pintype "passive"))
      (node (ref "RN2") (pin "5") (pinfunction "5_5") (pintype "passive"))
    )
    (net (code "100") (name "Net-(RN1F-1)") (class "Default")
      (node (ref "JP14") (pin "8") (pinfunction "8_8") (pintype "passive"))
      (node (ref "JP2") (pin "6") (pinfunction "6_6") (pintype "passive"))
      (node (ref "RN1") (pin "6") (pinfunction "1_6") (pintype "passive"))
      (node (ref "RN2") (pin "4") (pinfunction "4_4") (pintype "passive"))
    )
    (net (code "101") (name "Net-(RN1G-1)") (class "Default")
      (node (ref "JP14") (pin "9") (pinfunction "9_9") (pintype "passive"))
      (node (ref "JP2") (pin "7") (pinfunction "7_7") (pintype "passive"))
      (node (ref "RN1") (pin "7") (pinfunction "1_7") (pintype "passive"))
      (node (ref "RN2") (pin "3") (pinfunction "3_3") (pintype "passive"))
    )
    (net (code "102") (name "Net-(RN1H-1)") (class "Default")
      (node (ref "JP14") (pin "10") (pinfunction "10_10") (pintype "passive"))
      (node (ref "JP2") (pin "8") (pinfunction "8_8") (pintype "passive"))
      (node (ref "RN1") (pin "8") (pinfunction "1_8") (pintype "passive"))
      (node (ref "RN2") (pin "2") (pinfunction "2_2") (pintype "passive"))
    )
    (net (code "103") (name "Net-(RN4B-1)") (class "Default")
      (node (ref "JP13") (pin "2") (pinfunction "2_2") (pintype "passive"))
      (node (ref "JP3") (pin "2") (pinfunction "2_2") (pintype "passive"))
      (node (ref "RN4") (pin "2") (pinfunction "1_2") (pintype "passive"))
      (node (ref "RN5") (pin "8") (pinfunction "8_8") (pintype "passive"))
    )
    (net (code "104") (name "Net-(RN4C-1)") (class "Default")
      (node (ref "JP13") (pin "3") (pinfunction "3_3") (pintype "passive"))
      (node (ref "JP3") (pin "3") (pinfunction "3_3") (pintype "passive"))
      (node (ref "RN4") (pin "3") (pinfunction "1_3") (pintype "passive"))
      (node (ref "RN5") (pin "7") (pinfunction "7_7") (pintype "passive"))
    )
    (net (code "105") (name "Net-(RN4D-1)") (class "Default")
      (node (ref "JP13") (pin "4") (pinfunction "4_4") (pintype "passive"))
      (node (ref "JP3") (pin "4") (pinfunction "4_4") (pintype "passive"))
      (node (ref "RN4") (pin "4") (pinfunction "1_4") (pintype "passive"))
      (node (ref "RN5") (pin "6") (pinfunction "6_6") (pintype "passive"))
    )
    (net (code "106") (name "Net-(RN4E-1)") (class "Default")
      (node (ref "JP13") (pin "7") (pinfunction "7_7") (pintype "passive"))
      (node (ref "JP3") (pin "5") (pinfunction "5_5") (pintype "passive"))
      (node (ref "RN4") (pin "5") (pinfunction "1_5") (pintype "passive"))
      (node (ref "RN5") (pin "5") (pinfunction "5_5") (pintype "passive"))
    )
    (net (code "107") (name "Net-(RN4F-1)") (class "Default")
      (node (ref "JP13") (pin "8") (pinfunction "8_8") (pintype "passive"))
      (node (ref "JP3") (pin "6") (pinfunction "6_6") (pintype "passive"))
      (node (ref "RN4") (pin "6") (pinfunction "1_6") (pintype "passive"))
      (node (ref "RN5") (pin "4") (pinfunction "4_4") (pintype "passive"))
    )
    (net (code "108") (name "Net-(RN4G-1)") (class "Default")
      (node (ref "JP13") (pin "9") (pinfunction "9_9") (pintype "passive"))
      (node (ref "JP3") (pin "7") (pinfunction "7_7") (pintype "passive"))
      (node (ref "RN4") (pin "7") (pinfunction "1_7") (pintype "passive"))
      (node (ref "RN5") (pin "3") (pinfunction "3_3") (pintype "passive"))
    )
    (net (code "109") (name "Net-(RN4H-1)") (class "Default")
      (node (ref "JP13") (pin "10") (pinfunction "10_10") (pintype "passive"))
      (node (ref "JP3") (pin "8") (pinfunction "8_8") (pintype "passive"))
      (node (ref "RN4") (pin "8") (pinfunction "1_8") (pintype "passive"))
      (node (ref "RN5") (pin "2") (pinfunction "2_2") (pintype "passive"))
    )
    (net (code "110") (name "unconnected-(H1-MOUNT-PadB3,3)") (class "Default")
      (node (ref "H1") (pin "B3,3") (pinfunction "MOUNT_B3,3") (pintype "passive"))
    )
    (net (code "111") (name "unconnected-(H2-MOUNT-PadB3,3)") (class "Default")
      (node (ref "H2") (pin "B3,3") (pinfunction "MOUNT_B3,3") (pintype "passive"))
    )
    (net (code "112") (name "unconnected-(H3-MOUNT-PadB3,3)") (class "Default")
      (node (ref "H3") (pin "B3,3") (pinfunction "MOUNT_B3,3") (pintype "passive"))
    )
    (net (code "113") (name "unconnected-(H4-MOUNT-PadB3,3)") (class "Default")
      (node (ref "H4") (pin "B3,3") (pinfunction "MOUNT_B3,3") (pintype "passive"))
    )
    (net (code "114") (name "unconnected-(IC3A-QH*-Pad9)") (class "Default")
      (node (ref "IC3") (pin "9") (pinfunction "QH*_9") (pintype "tri_state"))
    )
    (net (code "115") (name "unconnected-(IC5A-QH*-Pad9)") (class "Default")
      (node (ref "IC5") (pin "9") (pinfunction "QH*_9") (pintype "tri_state"))
    )
    (net (code "116") (name "unconnected-(IC6A-+IN-Pad3)") (class "Default")
      (node (ref "IC6") (pin "3") (pinfunction "+IN_3") (pintype "input"))
    )
    (net (code "117") (name "unconnected-(IC6B-+IN-Pad5)") (class "Default")
      (node (ref "IC6") (pin "5") (pinfunction "+IN_5") (pintype "input"))
    )
    (net (code "118") (name "unconnected-(IC6C-+IN-Pad10)") (class "Default")
      (node (ref "IC6") (pin "10") (pinfunction "+IN_10") (pintype "input"))
    )
    (net (code "119") (name "unconnected-(IC6D-+IN-Pad12)") (class "Default")
      (node (ref "IC6") (pin "12") (pinfunction "+IN_12") (pintype "input"))
    )
    (net (code "120") (name "unconnected-(IC7-RS-Pad8)") (class "Default")
      (node (ref "IC7") (pin "8") (pinfunction "RS_8") (pintype "input"))
    )
    (net (code "121") (name "unconnected-(IC7-VREF-Pad5)") (class "Default")
      (node (ref "IC7") (pin "5") (pinfunction "VREF_5") (pintype "output"))
    )
    (net (code "122") (name "unconnected-(IC9A-+IN-Pad3)") (class "Default")
      (node (ref "IC9") (pin "3") (pinfunction "+IN_3") (pintype "input"))
    )
    (net (code "123") (name "unconnected-(IC9B-+IN-Pad5)") (class "Default")
      (node (ref "IC9") (pin "5") (pinfunction "+IN_5") (pintype "input"))
    )
    (net (code "124") (name "unconnected-(IC9C-+IN-Pad10)") (class "Default")
      (node (ref "IC9") (pin "10") (pinfunction "+IN_10") (pintype "input"))
    )
    (net (code "125") (name "unconnected-(IC9D-+IN-Pad12)") (class "Default")
      (node (ref "IC9") (pin "12") (pinfunction "+IN_12") (pintype "input"))
    )
    (net (code "126") (name "unconnected-(J3-Pad2)") (class "Default")
      (node (ref "J3") (pin "2") (pinfunction "2_2") (pintype "passive"))
    )
    (net (code "127") (name "unconnected-(JP4-Pad1)") (class "Default")
      (node (ref "JP4") (pin "1") (pinfunction "1_1") (pintype "passive"))
    )
    (net (code "128") (name "unconnected-(JP4-Pad2)") (class "Default")
      (node (ref "JP4") (pin "2") (pinfunction "2_2") (pintype "passive"))
    )
    (net (code "129") (name "unconnected-(JP4-Pad3)") (class "Default")
      (node (ref "JP4") (pin "3") (pinfunction "3_3") (pintype "passive"))
    )
    (net (code "130") (name "unconnected-(JP4-Pad4)") (class "Default")
      (node (ref "JP4") (pin "4") (pinfunction "4_4") (pintype "passive"))
    )
    (net (code "131") (name "unconnected-(JP7-Pad1)") (class "Default")
      (node (ref "JP7") (pin "1") (pinfunction "1_1") (pintype "passive"))
    )
    (net (code "132") (name "unconnected-(JP7-Pad2)") (class "Default")
      (node (ref "JP7") (pin "2") (pinfunction "2_2") (pintype "passive"))
    )
    (net (code "133") (name "unconnected-(JP7-Pad3)") (class "Default")
      (node (ref "JP7") (pin "3") (pinfunction "3_3") (pintype "passive"))
    )
    (net (code "134") (name "unconnected-(JP7-Pad4)") (class "Default")
      (node (ref "JP7") (pin "4") (pinfunction "4_4") (pintype "passive"))
    )
    (net (code "135") (name "unconnected-(JP7-Pad5)") (class "Default")
      (node (ref "JP7") (pin "5") (pinfunction "5_5") (pintype "passive"))
    )
    (net (code "136") (name "unconnected-(JP7-Pad6)") (class "Default")
      (node (ref "JP7") (pin "6") (pinfunction "6_6") (pintype "passive"))
    )
    (net (code "137") (name "unconnected-(JP8-Pad1)") (class "Default")
      (node (ref "JP8") (pin "1") (pinfunction "1_1") (pintype "passive"))
    )
    (net (code "138") (name "unconnected-(JP8-Pad2)") (class "Default")
      (node (ref "JP8") (pin "2") (pinfunction "2_2") (pintype "passive"))
    )
    (net (code "139") (name "unconnected-(JP8-Pad3)") (class "Default")
      (node (ref "JP8") (pin "3") (pinfunction "3_3") (pintype "passive"))
    )
    (net (code "140") (name "unconnected-(JP8-Pad4)") (class "Default")
      (node (ref "JP8") (pin "4") (pinfunction "4_4") (pintype "passive"))
    )
    (net (code "141") (name "unconnected-(JP9-Pad1)") (class "Default")
      (node (ref "JP9") (pin "1") (pinfunction "1_1") (pintype "passive"))
    )
    (net (code "142") (name "unconnected-(JP9-Pad2)") (class "Default")
      (node (ref "JP9") (pin "2") (pinfunction "2_2") (pintype "passive"))
    )
    (net (code "143") (name "unconnected-(JP9-Pad3)") (class "Default")
      (node (ref "JP9") (pin "3") (pinfunction "3_3") (pintype "passive"))
    )
    (net (code "144") (name "unconnected-(JP9-Pad4)") (class "Default")
      (node (ref "JP9") (pin "4") (pinfunction "4_4") (pintype "passive"))
    )
    (net (code "145") (name "unconnected-(JP10-Pad1)") (class "Default")
      (node (ref "JP10") (pin "1") (pinfunction "1_1") (pintype "passive"))
    )
    (net (code "146") (name "unconnected-(JP10-Pad2)") (class "Default")
      (node (ref "JP10") (pin "2") (pinfunction "2_2") (pintype "passive"))
    )
    (net (code "147") (name "unconnected-(JP10-Pad3)") (class "Default")
      (node (ref "JP10") (pin "3") (pinfunction "3_3") (pintype "passive"))
    )
    (net (code "148") (name "unconnected-(JP10-Pad4)") (class "Default")
      (node (ref "JP10") (pin "4") (pinfunction "4_4") (pintype "passive"))
    )
    (net (code "149") (name "unconnected-(JP11-Pad1)") (class "Default")
      (node (ref "JP11") (pin "1") (pinfunction "1_1") (pintype "passive"))
    )
    (net (code "150") (name "unconnected-(JP11-Pad2)") (class "Default")
      (node (ref "JP11") (pin "2") (pinfunction "2_2") (pintype "passive"))
    )
    (net (code "151") (name "unconnected-(JP11-Pad3)") (class "Default")
      (node (ref "JP11") (pin "3") (pinfunction "3_3") (pintype "passive"))
    )
    (net (code "152") (name "unconnected-(JP11-Pad4)") (class "Default")
      (node (ref "JP11") (pin "4") (pinfunction "4_4") (pintype "passive"))
    )
    (net (code "153") (name "unconnected-(JP11-Pad5)") (class "Default")
      (node (ref "JP11") (pin "5") (pinfunction "5_5") (pintype "passive"))
    )
    (net (code "154") (name "unconnected-(JP11-Pad6)") (class "Default")
      (node (ref "JP11") (pin "6") (pinfunction "6_6") (pintype "passive"))
    )
    (net (code "155") (name "unconnected-(JP13-Pad5)") (class "Default")
      (node (ref "JP13") (pin "5") (pinfunction "5_5") (pintype "passive"))
    )
    (net (code "156") (name "unconnected-(JP13-Pad6)") (class "Default")
      (node (ref "JP13") (pin "6") (pinfunction "6_6") (pintype "passive"))
    )
    (net (code "157") (name "unconnected-(JP14-Pad5)") (class "Default")
      (node (ref "JP14") (pin "5") (pinfunction "5_5") (pintype "passive"))
    )
    (net (code "158") (name "unconnected-(JP14-Pad6)") (class "Default")
      (node (ref "JP14") (pin "6") (pinfunction "6_6") (pintype "passive"))
    )
    (net (code "159") (name "unconnected-(JP15-Pad5)") (class "Default")
      (node (ref "JP15") (pin "5") (pinfunction "5_5") (pintype "passive"))
    )
    (net (code "160") (name "unconnected-(JP15-Pad6)") (class "Default")
      (node (ref "JP15") (pin "6") (pinfunction "6_6") (pintype "passive"))
    )
    (net (code "161") (name "unconnected-(U$1-PadBOOT0)") (class "Default")
      (node (ref "U$1") (pin "BOOT0") (pinfunction "BOOT0_BOOT0") (pintype "bidirectional"))
    )
    (net (code "162") (name "unconnected-(U$1-PadIOREF2)") (class "Default")
      (node (ref "U$1") (pin "IOREF2") (pinfunction "IOREF2_IOREF2") (pintype "input"))
    )
    (net (code "163") (name "unconnected-(U$1-PadNC1-PF7)") (class "Default")
      (node (ref "U$1") (pin "NC1-PF7") (pinfunction "NC1-PF7_NC1-PF7") (pintype "bidirectional"))
    )
    (net (code "164") (name "unconnected-(U$1-PadNC2-PF6)") (class "Default")
      (node (ref "U$1") (pin "NC2-PF6") (pinfunction "NC2-PF6_NC2-PF6") (pintype "bidirectional"))
    )
    (net (code "165") (name "unconnected-(U$1-PadNC3)") (class "Default")
      (node (ref "U$1") (pin "NC3") (pinfunction "NC3_NC3") (pintype "no_connect"))
    )
    (net (code "166") (name "unconnected-(U$1-PadNC4)") (class "Default")
      (node (ref "U$1") (pin "NC4") (pinfunction "NC4_NC4") (pintype "no_connect"))
    )
    (net (code "167") (name "unconnected-(U$1-PadNC5-PD8)") (class "Default")
      (node (ref "U$1") (pin "NC5-PD8") (pinfunction "NC5-PD8_NC5-PD8") (pintype "bidirectional"))
    )
    (net (code "168") (name "unconnected-(U$1-PadNC6-PB11)") (class "Default")
      (node (ref "U$1") (pin "NC6-PB11") (pinfunction "NC6-PB11_NC6-PB11") (pintype "no_connect"))
    )
    (net (code "169") (name "unconnected-(U$1-PadNC7-PF5)") (class "Default")
      (node (ref "U$1") (pin "NC7-PF5") (pinfunction "NC7-PF5_NC7-PF5") (pintype "bidirectional"))
    )
    (net (code "170") (name "unconnected-(U$1-PadNC8-PF4)") (class "Default")
      (node (ref "U$1") (pin "NC8-PF4") (pinfunction "NC8-PF4_NC8-PF4") (pintype "bidirectional"))
    )
    (net (code "171") (name "unconnected-(U$1-PadNRESET)") (class "Default")
      (node (ref "U$1") (pin "NRESET") (pinfunction "NRESET_NRESET") (pintype "input"))
    )
    (net (code "172") (name "unconnected-(U$1-PadPA0)") (class "Default")
      (node (ref "U$1") (pin "PA0") (pinfunction "PA0_PA0") (pintype "bidirectional"))
    )
    (net (code "173") (name "unconnected-(U$1-PadPA1)") (class "Default")
      (node (ref "U$1") (pin "PA1") (pinfunction "PA1_PA1") (pintype "bidirectional"))
    )
    (net (code "174") (name "unconnected-(U$1-PadPA2)") (class "Default")
      (node (ref "U$1") (pin "PA2") (pinfunction "PA2_PA2") (pintype "bidirectional"))
    )
    (net (code "175") (name "unconnected-(U$1-PadPA3)") (class "Default")
      (node (ref "U$1") (pin "PA3") (pinfunction "PA3_PA3") (pintype "bidirectional"))
    )
    (net (code "176") (name "unconnected-(U$1-PadPA4)") (class "Default")
      (node (ref "U$1") (pin "PA4") (pinfunction "PA4_PA4") (pintype "bidirectional"))
    )
    (net (code "177") (name "unconnected-(U$1-PadPA5)") (class "Default")
      (node (ref "U$1") (pin "PA5") (pinfunction "PA5_PA5") (pintype "bidirectional"))
    )
    (net (code "178") (name "unconnected-(U$1-PadPA6)") (class "Default")
      (node (ref "U$1") (pin "PA6") (pinfunction "PA6_PA6") (pintype "bidirectional"))
    )
    (net (code "179") (name "unconnected-(U$1-PadPA7)") (class "Default")
      (node (ref "U$1") (pin "PA7") (pinfunction "PA7_PA7") (pintype "bidirectional"))
    )
    (net (code "180") (name "unconnected-(U$1-PadPA8)") (class "Default")
      (node (ref "U$1") (pin "PA8") (pinfunction "PA8_PA8") (pintype "bidirectional"))
    )
    (net (code "181") (name "unconnected-(U$1-PadPA9)") (class "Default")
      (node (ref "U$1") (pin "PA9") (pinfunction "PA9_PA9") (pintype "bidirectional"))
    )
    (net (code "182") (name "unconnected-(U$1-PadPA10)") (class "Default")
      (node (ref "U$1") (pin "PA10") (pinfunction "PA10_PA10") (pintype "bidirectional"))
    )
    (net (code "183") (name "unconnected-(U$1-PadPA11)") (class "Default")
      (node (ref "U$1") (pin "PA11") (pinfunction "PA11_PA11") (pintype "bidirectional"))
    )
    (net (code "184") (name "unconnected-(U$1-PadPA12)") (class "Default")
      (node (ref "U$1") (pin "PA12") (pinfunction "PA12_PA12") (pintype "bidirectional"))
    )
    (net (code "185") (name "unconnected-(U$1-PadPA13)") (class "Default")
      (node (ref "U$1") (pin "PA13") (pinfunction "PA13_PA13") (pintype "bidirectional"))
    )
    (net (code "186") (name "unconnected-(U$1-PadPA14)") (class "Default")
      (node (ref "U$1") (pin "PA14") (pinfunction "PA14_PA14") (pintype "bidirectional"))
    )
    (net (code "187") (name "unconnected-(U$1-PadPA15)") (class "Default")
      (node (ref "U$1") (pin "PA15") (pinfunction "PA15_PA15") (pintype "bidirectional"))
    )
    (net (code "188") (name "unconnected-(U$1-PadPB0)") (class "Default")
      (node (ref "U$1") (pin "PB0") (pinfunction "PB0_PB0") (pintype "bidirectional"))
    )
    (net (code "189") (name "unconnected-(U$1-PadPB1)") (class "Default")
      (node (ref "U$1") (pin "PB1") (pinfunction "PB1_PB1") (pintype "bidirectional"))
    )
    (net (code "190") (name "unconnected-(U$1-PadPB2)") (class "Default")
      (node (ref "U$1") (pin "PB2") (pinfunction "PB2_PB2") (pintype "bidirectional"))
    )
    (net (code "191") (name "unconnected-(U$1-PadPB3)") (class "Default")
      (node (ref "U$1") (pin "PB3") (pinfunction "PB3_PB3") (pintype "bidirectional"))
    )
    (net (code "192") (name "unconnected-(U$1-PadPB4)") (class "Default")
      (node (ref "U$1") (pin "PB4") (pinfunction "PB4_PB4") (pintype "bidirectional"))
    )
    (net (code "193") (name "unconnected-(U$1-PadPB5)") (class "Default")
      (node (ref "U$1") (pin "PB5") (pinfunction "PB5_PB5") (pintype "bidirectional"))
    )
    (net (code "194") (name "unconnected-(U$1-PadPB6)") (class "Default")
      (node (ref "U$1") (pin "PB6") (pinfunction "PB6_PB6") (pintype "bidirectional"))
    )
    (net (code "195") (name "unconnected-(U$1-PadPB7)") (class "Default")
      (node (ref "U$1") (pin "PB7") (pinfunction "PB7_PB7") (pintype "bidirectional"))
    )
    (net (code "196") (name "unconnected-(U$1-PadPB10)") (class "Default")
      (node (ref "U$1") (pin "PB10") (pinfunction "PB10_PB10") (pintype "bidirectional"))
    )
    (net (code "197") (name "unconnected-(U$1-PadPB12)") (class "Default")
      (node (ref "U$1") (pin "PB12") (pinfunction "PB12_PB12") (pintype "bidirectional"))
    )
    (net (code "198") (name "unconnected-(U$1-PadPB13)") (class "Default")
      (node (ref "U$1") (pin "PB13") (pinfunction "PB13_PB13") (pintype "bidirectional"))
    )
    (net (code "199") (name "unconnected-(U$1-PadPB14)") (class "Default")
      (node (ref "U$1") (pin "PB14") (pinfunction "PB14_PB14") (pintype "bidirectional"))
    )
    (net (code "200") (name "unconnected-(U$1-PadPB15)") (class "Default")
      (node (ref "U$1") (pin "PB15") (pinfunction "PB15_PB15") (pintype "bidirectional"))
    )
    (net (code "201") (name "unconnected-(U$1-PadPC0)") (class "Default")
      (node (ref "U$1") (pin "PC0") (pinfunction "PC0_PC0") (pintype "bidirectional"))
    )
    (net (code "202") (name "unconnected-(U$1-PadPC1)") (class "Default")
      (node (ref "U$1") (pin "PC1") (pinfunction "PC1_PC1") (pintype "bidirectional"))
    )
    (net (code "203") (name "unconnected-(U$1-PadPC2)") (class "Default")
      (node (ref "U$1") (pin "PC2") (pinfunction "PC2_PC2") (pintype "bidirectional"))
    )
    (net (code "204") (name "unconnected-(U$1-PadPC3)") (class "Default")
      (node (ref "U$1") (pin "PC3") (pinfunction "PC3_PC3") (pintype "bidirectional"))
    )
    (net (code "205") (name "unconnected-(U$1-PadPC4)") (class "Default")
      (node (ref "U$1") (pin "PC4") (pinfunction "PC4_PC4") (pintype "bidirectional"))
    )
    (net (code "206") (name "unconnected-(U$1-PadPC5)") (class "Default")
      (node (ref "U$1") (pin "PC5") (pinfunction "PC5_PC5") (pintype "bidirectional"))
    )
    (net (code "207") (name "unconnected-(U$1-PadPC6)") (class "Default")
      (node (ref "U$1") (pin "PC6") (pinfunction "PC6_PC6") (pintype "bidirectional"))
    )
    (net (code "208") (name "unconnected-(U$1-PadPC7)") (class "Default")
      (node (ref "U$1") (pin "PC7") (pinfunction "PC7_PC7") (pintype "bidirectional"))
    )
    (net (code "209") (name "unconnected-(U$1-PadPC8)") (class "Default")
      (node (ref "U$1") (pin "PC8") (pinfunction "PC8_PC8") (pintype "bidirectional"))
    )
    (net (code "210") (name "unconnected-(U$1-PadPC9)") (class "Default")
      (node (ref "U$1") (pin "PC9") (pinfunction "PC9_PC9") (pintype "bidirectional"))
    )
    (net (code "211") (name "unconnected-(U$1-PadPC10)") (class "Default")
      (node (ref "U$1") (pin "PC10") (pinfunction "PC10_PC10") (pintype "bidirectional"))
    )
    (net (code "212") (name "unconnected-(U$1-PadPC11)") (class "Default")
      (node (ref "U$1") (pin "PC11") (pinfunction "PC11_PC11") (pintype "bidirectional"))
    )
    (net (code "213") (name "unconnected-(U$1-PadPC12)") (class "Default")
      (node (ref "U$1") (pin "PC12") (pinfunction "PC12_PC12") (pintype "bidirectional"))
    )
    (net (code "214") (name "unconnected-(U$1-PadPC13)") (class "Default")
      (node (ref "U$1") (pin "PC13") (pinfunction "PC13_PC13") (pintype "bidirectional"))
    )
    (net (code "215") (name "unconnected-(U$1-PadPC14)") (class "Default")
      (node (ref "U$1") (pin "PC14") (pinfunction "PC14_PC14") (pintype "bidirectional"))
    )
    (net (code "216") (name "unconnected-(U$1-PadPC15)") (class "Default")
      (node (ref "U$1") (pin "PC15") (pinfunction "PC15_PC15") (pintype "bidirectional"))
    )
    (net (code "217") (name "unconnected-(U$1-PadPD2)") (class "Default")
      (node (ref "U$1") (pin "PD2") (pinfunction "PD2_PD2") (pintype "bidirectional"))
    )
    (net (code "218") (name "unconnected-(U$1-PadPF0-PH0)") (class "Default")
      (node (ref "U$1") (pin "PF0-PH0") (pinfunction "PF0-PH0_PF0-PH0") (pintype "bidirectional"))
    )
    (net (code "219") (name "unconnected-(U$1-PadPF1-PH1)") (class "Default")
      (node (ref "U$1") (pin "PF1-PH1") (pinfunction "PF1-PH1_PF1-PH1") (pintype "bidirectional"))
    )
  )
)
